# DOOR.net
KiCad netlist of a schematic drawn in Altium Designer
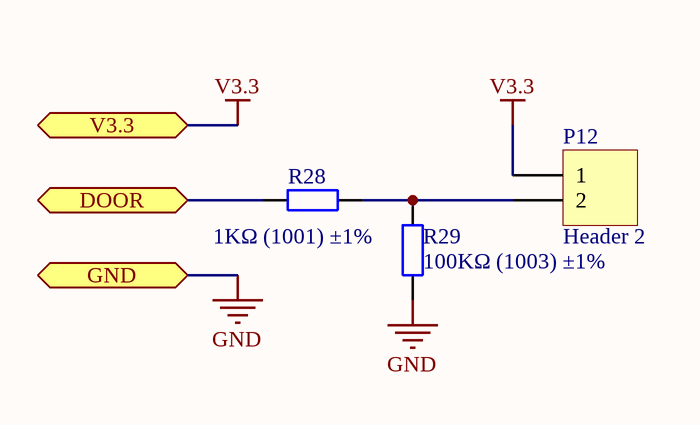
[diagram p0: DOOR.SchDoc]

(export (version "E")
  (design (tool "Eeschema 10.0.6"))
  (components
    (comp (ref "P12")
      (value "Header 2")
      (footprint "2P_XH2.54")
      (description "Header, 2-Pin")
      (fields (field (name "PUBLISHER") "Altium Limited"))
      (libsource (lib "Miscellaneous Connectors") (part "Header 2"))
    )
    (comp (ref "R28")
      (value "1KΩ (1001) ±1%")
      (footprint "0805_R")
      (description "贴片电阻")
      (libsource (lib "Miscellaneous Devices LC") (part "0805 1KΩ (1001) 1%"))
    )
    (comp (ref "R29")
      (value "100KΩ (1003) ±1%")
      (footprint "0805_R")
      (description "贴片电阻")
      (libsource (lib "Miscellaneous Devices LC") (part "0805 100KΩ (1003) 1%"))
    )
  )
  (nets
    (net (code "1") (name "/DOOR") (class "Default")
      (node (ref "R28") (pin "1") (pinfunction "1_1") (pintype "passive"))
    )
    (net (code "2") (name "GND") (class "Default")
      (node (ref "R29") (pin "2") (pinfunction "2_2") (pintype "passive"))
    )
    (net (code "3") (name "Net-(P12-Pad2)") (class "Default")
      (node (ref "P12") (pin "2") (pinfunction "2_2") (pintype "passive"))
      (node (ref "R28") (pin "2") (pinfunction "2_2") (pintype "passive"))
      (node (ref "R29") (pin "1") (pinfunction "1_1") (pintype "passive"))
    )
    (net (code "4") (name "V3.3") (class "Default")
      (node (ref "P12") (pin "1") (pinfunction "1_1") (pintype "passive"))
    )
  )
)
